# AQCA-Light-Control-uC-A0.net
KiCad netlist of a schematic drawn in Altium Designer
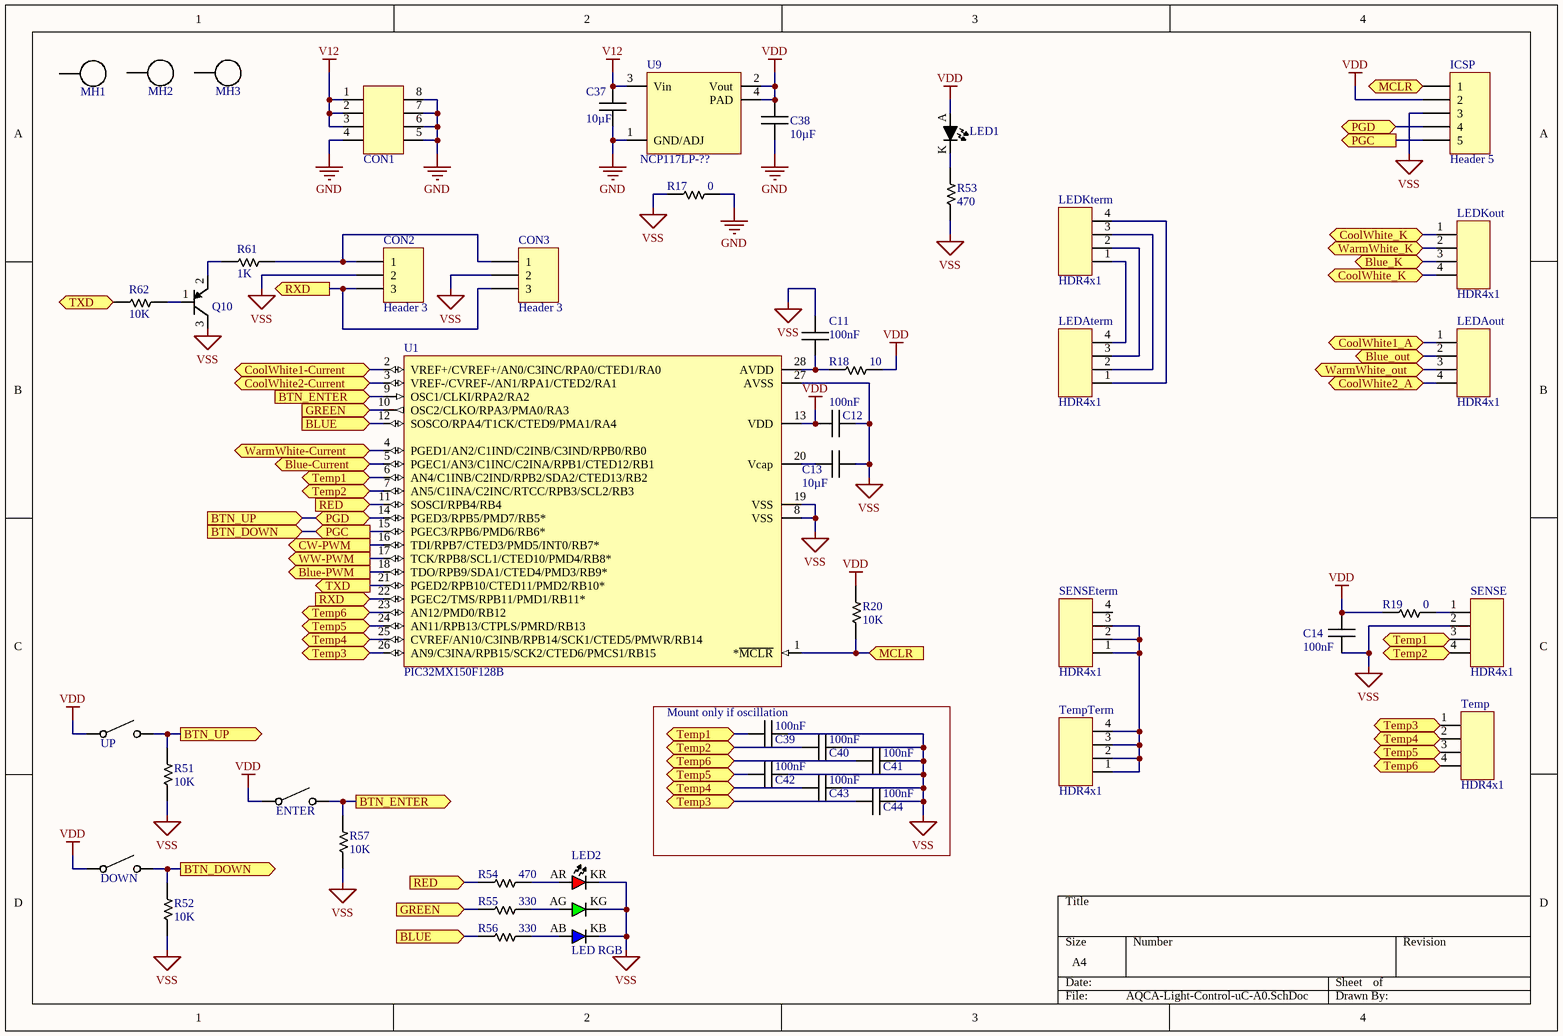
[diagram p0: AQCA-Light-Control-uC-A0.SchDoc]

(export (version "E")
  (design (tool "Eeschema 10.0.6"))
  (components
    (comp (ref "C11")
      (value "100nF")
      (footprint "CAPC1608N")
      (fields (field (name "VOLTAGE") "16V"))
      (libsource (lib "Megaxone") (part "Capacitor"))
    )
    (comp (ref "C12")
      (value "100nF")
      (footprint "CAPC1608N")
      (fields (field (name "VOLTAGE") "16V"))
      (libsource (lib "Megaxone") (part "Capacitor"))
    )
    (comp (ref "C13")
      (value "10µF")
      (footprint "CAPC2012N")
      (fields (field (name "VOLTAGE") "16V"))
      (libsource (lib "Megaxone") (part "Capacitor"))
    )
    (comp (ref "C14")
      (value "100nF")
      (footprint "CAPC1608N")
      (fields (field (name "VOLTAGE") "16V"))
      (libsource (lib "Megaxone") (part "Capacitor"))
    )
    (comp (ref "C37")
      (value "10µF")
      (footprint "CAPC3225N")
      (fields (field (name "VOLTAGE") "25V"))
      (libsource (lib "Megaxone") (part "Capacitor"))
    )
    (comp (ref "C38")
      (value "10µF")
      (footprint "CAPC3225N")
      (fields (field (name "VOLTAGE") "25V"))
      (libsource (lib "Megaxone") (part "Capacitor"))
    )
    (comp (ref "C39")
      (value "100nF")
      (footprint "CAPC1608N")
      (fields (field (name "VOLTAGE") "16V"))
      (libsource (lib "Megaxone") (part "Capacitor"))
    )
    (comp (ref "C40")
      (value "100nF")
      (footprint "CAPC1608N")
      (fields (field (name "VOLTAGE") "16V"))
      (libsource (lib "Megaxone") (part "Capacitor"))
    )
    (comp (ref "C41")
      (value "100nF")
      (footprint "CAPC1608N")
      (fields (field (name "VOLTAGE") "16V"))
      (libsource (lib "Megaxone") (part "Capacitor"))
    )
    (comp (ref "C42")
      (value "100nF")
      (footprint "CAPC1608N")
      (fields (field (name "VOLTAGE") "16V"))
      (libsource (lib "Megaxone") (part "Capacitor"))
    )
    (comp (ref "C43")
      (value "100nF")
      (footprint "CAPC1608N")
      (fields (field (name "VOLTAGE") "16V"))
      (libsource (lib "Megaxone") (part "Capacitor"))
    )
    (comp (ref "C44")
      (value "100nF")
      (footprint "CAPC1608N")
      (fields (field (name "VOLTAGE") "16V"))
      (libsource (lib "Megaxone") (part "Capacitor"))
    )
    (comp (ref "CON1")
      (value "Molex Mini-Fit 8pin")
      (footprint "Molex Mini-Fit 8pin")
      (libsource (lib "Megaxone") (part "Molex Mini-Fit 8pin"))
    )
    (comp (ref "CON2")
      (value "Header 3")
      (footprint "HDR1X3")
      (description "Header, 3-Pin")
      (fields (field (name "PUBLISHER") "Altium Limited"))
      (libsource (lib "Miscellaneous Connectors") (part "Header 3"))
    )
    (comp (ref "CON3")
      (value "Header 3")
      (footprint "HDR1X3")
      (description "Header, 3-Pin")
      (fields (field (name "PUBLISHER") "Altium Limited"))
      (libsource (lib "Miscellaneous Connectors") (part "Header 3"))
    )
    (comp (ref "DOWN")
      (value "Tact Button NO")
      (footprint "TACT SMD 4.5×4.5mm")
      (libsource (lib "Megaxone") (part "Tact Button NO"))
    )
    (comp (ref "ENTER")
      (value "Tact Button NO")
      (footprint "TACT SMD 4.5×4.5mm")
      (libsource (lib "Megaxone") (part "Tact Button NO"))
    )
    (comp (ref "ICSP")
      (value "Header 5")
      (footprint "HDR1X5")
      (description "Header, 5-Pin")
      (fields (field (name "PUBLISHER") "Altium Limited"))
      (libsource (lib "Miscellaneous Connectors") (part "Header 5"))
    )
    (comp (ref "LED1") (value "~") (footprint "LED 3216m") (libsource (lib "Megaxone") (part "LED")))
    (comp (ref "LED2")
      (value "LED RGB")
      (footprint "LED PLCC-6")
      (libsource (lib "Megaxone") (part "LED RGB"))
    )
    (comp (ref "LEDAout")
      (value "HDR4x1")
      (footprint "HDR4x1 EDGE female")
      (libsource (lib "") (part "HDR4x1_1"))
    )
    (comp (ref "LEDAterm")
      (value "HDR4x1")
      (footprint "HDR4x1 EDGE male")
      (libsource (lib "Megaxone") (part "HDR4x1"))
    )
    (comp (ref "LEDKout")
      (value "HDR4x1")
      (footprint "HDR4x1 EDGE female")
      (libsource (lib "") (part "HDR4x1_1"))
    )
    (comp (ref "LEDKterm")
      (value "HDR4x1")
      (footprint "HDR4x1 EDGE male")
      (libsource (lib "Megaxone") (part "HDR4x1"))
    )
    (comp (ref "MH1")
      (value "Mounting Hole")
      (footprint "Mount Hole 4-6.5")
      (libsource (lib "Megaxone") (part "Mounting Hole"))
    )
    (comp (ref "MH2")
      (value "Mounting Hole")
      (footprint "Mount Hole 4-6.5")
      (libsource (lib "Megaxone") (part "Mounting Hole"))
    )
    (comp (ref "MH3")
      (value "Mounting Hole")
      (footprint "Mount Hole 4-6.5")
      (libsource (lib "Megaxone") (part "Mounting Hole"))
    )
    (comp (ref "Q10") (value "*") (footprint "SOT23_N") (libsource (lib "Megaxone") (part "PNP")))
    (comp (ref "R17") (value "0") (footprint "RESC1608N") (libsource (lib "Megaxone") (part "Resistor")))
    (comp (ref "R18") (value "10") (footprint "RESC1608N") (libsource (lib "Megaxone") (part "Resistor")))
    (comp (ref "R19") (value "0") (footprint "RESC1608N") (libsource (lib "Megaxone") (part "Resistor")))
    (comp (ref "R20") (value "10K") (footprint "RESC1608N") (libsource (lib "") (part "Resistor_1")))
    (comp (ref "R51") (value "10K") (footprint "RESC1608N") (libsource (lib "") (part "Resistor_1")))
    (comp (ref "R52") (value "10K") (footprint "RESC1608N") (libsource (lib "") (part "Resistor_1")))
    (comp (ref "R53") (value "470") (footprint "RESC1608N") (libsource (lib "") (part "Resistor_1")))
    (comp (ref "R54") (value "470") (footprint "RESC1608N") (libsource (lib "Megaxone") (part "Resistor")))
    (comp (ref "R55") (value "330") (footprint "RESC1608N") (libsource (lib "Megaxone") (part "Resistor")))
    (comp (ref "R56") (value "330") (footprint "RESC1608N") (libsource (lib "Megaxone") (part "Resistor")))
    (comp (ref "R57") (value "10K") (footprint "RESC1608N") (libsource (lib "") (part "Resistor_1")))
    (comp (ref "R61") (value "1K") (footprint "RESC1608N") (libsource (lib "Megaxone") (part "Resistor")))
    (comp (ref "R62") (value "10K") (footprint "RESC1608N") (libsource (lib "Megaxone") (part "Resistor")))
    (comp (ref "SENSE")
      (value "HDR4x1")
      (footprint "HDR4x1 EDGE female")
      (libsource (lib "") (part "HDR4x1_1"))
    )
    (comp (ref "SENSEterm")
      (value "HDR4x1")
      (footprint "HDR4x1 EDGE male")
      (libsource (lib "Megaxone") (part "HDR4x1"))
    )
    (comp (ref "Temp")
      (value "HDR4x1")
      (footprint "HDR4x1 EDGE female")
      (libsource (lib "") (part "HDR4x1_1"))
    )
    (comp (ref "TempTerm")
      (value "HDR4x1")
      (footprint "HDR4x1 EDGE male")
      (libsource (lib "Megaxone") (part "HDR4x1"))
    )
    (comp (ref "U1")
      (value "PIC32MX150F128B")
      (footprint "SSOP28_N")
      (libsource (lib "Megaxone") (part "PIC32MX120FxxxB"))
    )
    (comp (ref "U9")
      (value "NCP117LP-??")
      (footprint "SOT223-4N")
      (libsource (lib "Megaxone") (part "NCP1117LP"))
    )
    (comp (ref "UP")
      (value "Tact Button NO")
      (footprint "TACT SMD 4.5×4.5mm")
      (libsource (lib "Megaxone") (part "Tact Button NO"))
    )
  )
  (nets
    (net (code "1") (name "/BLUE") (class "Default")
      (node (ref "R56") (pin "1") (pinfunction "1_1") (pintype "passive"))
      (node (ref "U1") (pin "12") (pinfunction "SOSCO/RPA4/T1CK/CTED9/PMA1/RA4_12") (pintype "bidirectional"))
    )
    (net (code "2") (name "/BTN_DOWN") (class "Default")
      (node (ref "DOWN") (pin "2") (pinfunction "2_2") (pintype "passive"))
      (node (ref "ICSP") (pin "5") (pinfunction "5_5") (pintype "passive"))
      (node (ref "R52") (pin "2") (pinfunction "2_2") (pintype "passive"))
      (node (ref "U1") (pin "15") (pinfunction "PGEC3/RPB6/PMD6/RB6*_15") (pintype "bidirectional"))
    )
    (net (code "3") (name "/BTN_ENTER") (class "Default")
      (node (ref "ENTER") (pin "2") (pinfunction "2_2") (pintype "passive"))
      (node (ref "R57") (pin "2") (pinfunction "2_2") (pintype "passive"))
      (node (ref "U1") (pin "9") (pinfunction "OSC1/CLKI/RPA2/RA2_9") (pintype "input"))
    )
    (net (code "4") (name "/BTN_UP") (class "Default")
      (node (ref "ICSP") (pin "4") (pinfunction "4_4") (pintype "passive"))
      (node (ref "R51") (pin "2") (pinfunction "2_2") (pintype "passive"))
      (node (ref "U1") (pin "14") (pinfunction "PGED3/RPB5/PMD7/RB5*_14") (pintype "bidirectional"))
      (node (ref "UP") (pin "2") (pinfunction "2_2") (pintype "passive"))
    )
    (net (code "5") (name "/Blue-Current") (class "Default")
      (node (ref "U1") (pin "5") (pinfunction "PGEC1/AN3/C1INC/C2INA/RPB1/CTED12/RB1_5") (pintype "bidirectional"))
    )
    (net (code "6") (name "/Blue-PWM") (class "Default")
      (node (ref "U1") (pin "18") (pinfunction "TDO/RPB9/SDA1/CTED4/PMD3/RB9*_18") (pintype "bidirectional"))
    )
    (net (code "7") (name "/Blue_K") (class "Default")
      (node (ref "LEDKout") (pin "3") (pinfunction "3_3") (pintype "passive"))
    )
    (net (code "8") (name "/Blue_out") (class "Default")
      (node (ref "LEDAout") (pin "2") (pinfunction "2_2") (pintype "passive"))
    )
    (net (code "9") (name "/CW-PWM") (class "Default")
      (node (ref "U1") (pin "16") (pinfunction "TDI/RPB7/CTED3/PMD5/INT0/RB7*_16") (pintype "bidirectional"))
    )
    (net (code "10") (name "/CoolWhite1-Current") (class "Default")
      (node (ref "U1") (pin "2") (pinfunction "VREF+/CVREF+/AN0/C3INC/RPA0/CTED1/RA0_2") (pintype "bidirectional"))
    )
    (net (code "11") (name "/CoolWhite1_A") (class "Default")
      (node (ref "LEDAout") (pin "1") (pinfunction "1_1") (pintype "passive"))
    )
    (net (code "12") (name "/CoolWhite2-Current") (class "Default")
      (node (ref "U1") (pin "3") (pinfunction "VREF-/CVREF-/AN1/RPA1/CTED2/RA1_3") (pintype "bidirectional"))
    )
    (net (code "13") (name "/CoolWhite2_A") (class "Default")
      (node (ref "LEDAout") (pin "4") (pinfunction "4_4") (pintype "passive"))
    )
    (net (code "14") (name "/CoolWhite_K") (class "Default")
      (node (ref "LEDKout") (pin "1") (pinfunction "1_1") (pintype "passive"))
      (node (ref "LEDKout") (pin "4") (pinfunction "4_4") (pintype "passive"))
    )
    (net (code "15") (name "/GREEN") (class "Default")
      (node (ref "R55") (pin "1") (pinfunction "1_1") (pintype "passive"))
      (node (ref "U1") (pin "10") (pinfunction "OSC2/CLKO/RPA3/PMA0/RA3_10") (pintype "output"))
    )
    (net (code "16") (name "/MCLR") (class "Default")
      (node (ref "ICSP") (pin "1") (pinfunction "1_1") (pintype "passive"))
      (node (ref "R20") (pin "1") (pinfunction "1_1") (pintype "passive"))
      (node (ref "U1") (pin "1") (pinfunction "*~{MCLR}_1") (pintype "input"))
    )
    (net (code "17") (name "/RED") (class "Default")
      (node (ref "R54") (pin "1") (pinfunction "1_1") (pintype "passive"))
      (node (ref "U1") (pin "11") (pinfunction "SOSCI/RPB4/RB4_11") (pintype "bidirectional"))
    )
    (net (code "18") (name "/RXD") (class "Default")
      (node (ref "CON2") (pin "3") (pinfunction "3_3") (pintype "passive"))
      (node (ref "CON3") (pin "3") (pinfunction "3_3") (pintype "passive"))
      (node (ref "U1") (pin "22") (pinfunction "PGEC2/TMS/RPB11/PMD1/RB11*_22") (pintype "bidirectional"))
    )
    (net (code "19") (name "/TXD") (class "Default")
      (node (ref "R62") (pin "1") (pinfunction "1_1") (pintype "passive"))
      (node (ref "U1") (pin "21") (pinfunction "PGED2/RPB10/CTED11/PMD2/RB10*_21") (pintype "bidirectional"))
    )
    (net (code "20") (name "/Temp1") (class "Default")
      (node (ref "C39") (pin "1") (pinfunction "1_1") (pintype "passive"))
      (node (ref "SENSE") (pin "3") (pinfunction "3_3") (pintype "passive"))
      (node (ref "U1") (pin "6") (pinfunction "AN4/C1INB/C2IND/RPB2/SDA2/CTED13/RB2_6") (pintype "bidirectional"))
    )
    (net (code "21") (name "/Temp2") (class "Default")
      (node (ref "C40") (pin "1") (pinfunction "1_1") (pintype "passive"))
      (node (ref "SENSE") (pin "4") (pinfunction "4_4") (pintype "passive"))
      (node (ref "U1") (pin "7") (pinfunction "AN5/C1INA/C2INC/RTCC/RPB3/SCL2/RB3_7") (pintype "bidirectional"))
    )
    (net (code "22") (name "/Temp3") (class "Default")
      (node (ref "C44") (pin "1") (pinfunction "1_1") (pintype "passive"))
      (node (ref "Temp") (pin "1") (pinfunction "1_1") (pintype "passive"))
      (node (ref "U1") (pin "26") (pinfunction "AN9/C3INA/RPB15/SCK2/CTED6/PMCS1/RB15_26") (pintype "bidirectional"))
    )
    (net (code "23") (name "/Temp4") (class "Default")
      (node (ref "C43") (pin "1") (pinfunction "1_1") (pintype "passive"))
      (node (ref "Temp") (pin "2") (pinfunction "2_2") (pintype "passive"))
      (node (ref "U1") (pin "25") (pinfunction "CVREF/AN10/C3INB/RPB14/SCK1/CTED5/PMWR/RB14_25") (pintype "bidirectional"))
    )
    (net (code "24") (name "/Temp5") (class "Default")
      (node (ref "C42") (pin "1") (pinfunction "1_1") (pintype "passive"))
      (node (ref "Temp") (pin "3") (pinfunction "3_3") (pintype "passive"))
      (node (ref "U1") (pin "24") (pinfunction "AN11/RPB13/CTPLS/PMRD/RB13_24") (pintype "bidirectional"))
    )
    (net (code "25") (name "/Temp6") (class "Default")
      (node (ref "C41") (pin "1") (pinfunction "1_1") (pintype "passive"))
      (node (ref "Temp") (pin "4") (pinfunction "4_4") (pintype "passive"))
      (node (ref "U1") (pin "23") (pinfunction "AN12/PMD0/RB12_23") (pintype "bidirectional"))
    )
    (net (code "26") (name "/WW-PWM") (class "Default")
      (node (ref "U1") (pin "17") (pinfunction "TCK/RPB8/SCL1/CTED10/PMD4/RB8*_17") (pintype "bidirectional"))
    )
    (net (code "27") (name "/WarmWhite-Current") (class "Default")
      (node (ref "U1") (pin "4") (pinfunction "PGED1/AN2/C1IND/C2INB/C3IND/RPB0/RB0_4") (pintype "bidirectional"))
    )
    (net (code "28") (name "/WarmWhite_K") (class "Default")
      (node (ref "LEDKout") (pin "2") (pinfunction "2_2") (pintype "passive"))
    )
    (net (code "29") (name "/WarmWhite_out") (class "Default")
      (node (ref "LEDAout") (pin "3") (pinfunction "3_3") (pintype "passive"))
    )
    (net (code "30") (name "GND") (class "Default")
      (node (ref "C37") (pin "1") (pinfunction "1_1") (pintype "passive"))
      (node (ref "C38") (pin "1") (pinfunction "1_1") (pintype "passive"))
      (node (ref "CON1") (pin "4") (pintype "power_in"))
      (node (ref "CON1") (pin "5") (pintype "power_in"))
      (node (ref "CON1") (pin "6") (pintype "power_in"))
      (node (ref "CON1") (pin "7") (pintype "power_in"))
      (node (ref "CON1") (pin "8") (pintype "power_in"))
      (node (ref "R17") (pin "2") (pinfunction "2_2") (pintype "passive"))
      (node (ref "U9") (pin "1") (pinfunction "GND/ADJ_1") (pintype "power_in"))
    )
    (net (code "31") (name "Net-(CON2-Pad1)") (class "Default")
      (node (ref "CON2") (pin "1") (pinfunction "1_1") (pintype "passive"))
      (node (ref "CON3") (pin "1") (pinfunction "1_1") (pintype "passive"))
      (node (ref "R61") (pin "2") (pinfunction "2_2") (pintype "passive"))
    )
    (net (code "32") (name "Net-(LED1-PadK)") (class "Default")
      (node (ref "LED1") (pin "K") (pinfunction "K_K") (pintype "passive"))
      (node (ref "R53") (pin "2") (pinfunction "2_2") (pintype "passive"))
    )
    (net (code "33") (name "Net-(LED2-PadAB)") (class "Default")
      (node (ref "LED2") (pin "AB") (pinfunction "AB_AB") (pintype "passive"))
      (node (ref "R56") (pin "2") (pinfunction "2_2") (pintype "passive"))
    )
    (net (code "34") (name "Net-(LED2-PadAG)") (class "Default")
      (node (ref "LED2") (pin "AG") (pinfunction "AG_AG") (pintype "passive"))
      (node (ref "R55") (pin "2") (pinfunction "2_2") (pintype "passive"))
    )
    (net (code "35") (name "Net-(LED2-PadAR)") (class "Default")
      (node (ref "LED2") (pin "AR") (pinfunction "AR_AR") (pintype "passive"))
      (node (ref "R54") (pin "2") (pinfunction "2_2") (pintype "passive"))
    )
    (net (code "36") (name "Net-(LEDAterm-Pad1)") (class "Default")
      (node (ref "LEDAterm") (pin "1") (pinfunction "1_1") (pintype "passive"))
      (node (ref "LEDKterm") (pin "4") (pinfunction "4_4") (pintype "passive"))
    )
    (net (code "37") (name "Net-(LEDAterm-Pad2)") (class "Default")
      (node (ref "LEDAterm") (pin "2") (pinfunction "2_2") (pintype "passive"))
      (node (ref "LEDKterm") (pin "3") (pinfunction "3_3") (pintype "passive"))
    )
    (net (code "38") (name "Net-(LEDAterm-Pad3)") (class "Default")
      (node (ref "LEDAterm") (pin "3") (pinfunction "3_3") (pintype "passive"))
      (node (ref "LEDKterm") (pin "2") (pinfunction "2_2") (pintype "passive"))
    )
    (net (code "39") (name "Net-(LEDAterm-Pad4)") (class "Default")
      (node (ref "LEDAterm") (pin "4") (pinfunction "4_4") (pintype "passive"))
      (node (ref "LEDKterm") (pin "1") (pinfunction "1_1") (pintype "passive"))
    )
    (net (code "40") (name "Net-(Q10-B)") (class "Default")
      (node (ref "Q10") (pin "1") (pinfunction "B_1") (pintype "passive"))
      (node (ref "R62") (pin "2") (pinfunction "2_2") (pintype "passive"))
    )
    (net (code "41") (name "Net-(Q10-E)") (class "Default")
      (node (ref "Q10") (pin "2") (pinfunction "E_2") (pintype "passive"))
      (node (ref "R61") (pin "1") (pinfunction "1_1") (pintype "passive"))
    )
    (net (code "42") (name "Net-(R19-Pad2)") (class "Default")
      (node (ref "R19") (pin "2") (pinfunction "2_2") (pintype "passive"))
      (node (ref "SENSE") (pin "1") (pinfunction "1_1") (pintype "passive"))
    )
    (net (code "43") (name "Net-(SENSEterm-Pad1)") (class "Default")
      (node (ref "SENSEterm") (pin "1") (pinfunction "1_1") (pintype "passive"))
      (node (ref "SENSEterm") (pin "2") (pinfunction "2_2") (pintype "passive"))
      (node (ref "SENSEterm") (pin "3") (pinfunction "3_3") (pintype "passive"))
      (node (ref "TempTerm") (pin "1") (pinfunction "1_1") (pintype "passive"))
      (node (ref "TempTerm") (pin "2") (pinfunction "2_2") (pintype "passive"))
      (node (ref "TempTerm") (pin "3") (pinfunction "3_3") (pintype "passive"))
      (node (ref "TempTerm") (pin "4") (pinfunction "4_4") (pintype "passive"))
    )
    (net (code "44") (name "Net-(U1-AVDD)") (class "Default")
      (node (ref "C11") (pin "1") (pinfunction "1_1") (pintype "passive"))
      (node (ref "R18") (pin "1") (pinfunction "1_1") (pintype "passive"))
      (node (ref "U1") (pin "28") (pinfunction "AVDD_28") (pintype "power_in"))
    )
    (net (code "45") (name "Net-(U1-Vcap)") (class "Default")
      (node (ref "C13") (pin "1") (pinfunction "1_1") (pintype "passive"))
      (node (ref "U1") (pin "20") (pinfunction "Vcap_20") (pintype "power_in"))
    )
    (net (code "46") (name "V12") (class "Default")
      (node (ref "C37") (pin "2") (pinfunction "2_2") (pintype "passive"))
      (node (ref "CON1") (pin "1") (pintype "power_in"))
      (node (ref "CON1") (pin "2") (pintype "power_in"))
      (node (ref "CON1") (pin "3") (pintype "power_in"))
      (node (ref "U9") (pin "3") (pinfunction "Vin_3") (pintype "power_in"))
    )
    (net (code "47") (name "VDD") (class "Default")
      (node (ref "C12") (pin "1") (pinfunction "1_1") (pintype "passive"))
      (node (ref "C14") (pin "2") (pinfunction "2_2") (pintype "passive"))
      (node (ref "C38") (pin "2") (pinfunction "2_2") (pintype "passive"))
      (node (ref "DOWN") (pin "1") (pinfunction "1_1") (pintype "passive"))
      (node (ref "ENTER") (pin "1") (pinfunction "1_1") (pintype "passive"))
      (node (ref "ICSP") (pin "2") (pinfunction "2_2") (pintype "passive"))
      (node (ref "LED1") (pin "A") (pinfunction "A_A") (pintype "passive"))
      (node (ref "R18") (pin "2") (pinfunction "2_2") (pintype "passive"))
      (node (ref "R19") (pin "1") (pinfunction "1_1") (pintype "passive"))
      (node (ref "R20") (pin "2") (pinfunction "2_2") (pintype "passive"))
      (node (ref "U1") (pin "13") (pinfunction "VDD_13") (pintype "power_in"))
      (node (ref "U9") (pin "2") (pinfunction "Vout_2") (pintype "power_in"))
      (node (ref "U9") (pin "4") (pinfunction "PAD_4") (pintype "power_in"))
      (node (ref "UP") (pin "1") (pinfunction "1_1") (pintype "passive"))
    )
    (net (code "48") (name "VSS") (class "Default")
      (node (ref "C11") (pin "2") (pinfunction "2_2") (pintype "passive"))
      (node (ref "C12") (pin "2") (pinfunction "2_2") (pintype "passive"))
      (node (ref "C13") (pin "2") (pinfunction "2_2") (pintype "passive"))
      (node (ref "C14") (pin "1") (pinfunction "1_1") (pintype "passive"))
      (node (ref "C39") (pin "2") (pinfunction "2_2") (pintype "passive"))
      (node (ref "C40") (pin "2") (pinfunction "2_2") (pintype "passive"))
      (node (ref "C41") (pin "2") (pinfunction "2_2") (pintype "passive"))
      (node (ref "C42") (pin "2") (pinfunction "2_2") (pintype "passive"))
      (node (ref "C43") (pin "2") (pinfunction "2_2") (pintype "passive"))
      (node (ref "C44") (pin "2") (pinfunction "2_2") (pintype "passive"))
      (node (ref "CON2") (pin "2") (pinfunction "2_2") (pintype "passive"))
      (node (ref "CON3") (pin "2") (pinfunction "2_2") (pintype "passive"))
      (node (ref "ICSP") (pin "3") (pinfunction "3_3") (pintype "passive"))
      (node (ref "LED2") (pin "KB") (pinfunction "KB_KB") (pintype "passive"))
      (node (ref "LED2") (pin "KG") (pinfunction "KG_KG") (pintype "passive"))
      (node (ref "LED2") (pin "KR") (pinfunction "KR_KR") (pintype "passive"))
      (node (ref "Q10") (pin "3") (pinfunction "C_3") (pintype "passive"))
      (node (ref "R17") (pin "1") (pinfunction "1_1") (pintype "passive"))
      (node (ref "R51") (pin "1") (pinfunction "1_1") (pintype "passive"))
      (node (ref "R52") (pin "1") (pinfunction "1_1") (pintype "passive"))
      (node (ref "R53") (pin "1") (pinfunction "1_1") (pintype "passive"))
      (node (ref "R57") (pin "1") (pinfunction "1_1") (pintype "passive"))
      (node (ref "SENSE") (pin "2") (pinfunction "2_2") (pintype "passive"))
      (node (ref "U1") (pin "19") (pinfunction "VSS_19") (pintype "power_in"))
      (node (ref "U1") (pin "27") (pinfunction "AVSS_27") (pintype "power_in"))
      (node (ref "U1") (pin "8") (pinfunction "VSS_8") (pintype "power_in"))
    )
    (net (code "49") (name "unconnected-(MH1-Pad1)") (class "Default")
      (node (ref "MH1") (pin "1") (pintype "power_in"))
    )
    (net (code "50") (name "unconnected-(MH2-Pad1)") (class "Default")
      (node (ref "MH2") (pin "1") (pintype "power_in"))
    )
    (net (code "51") (name "unconnected-(MH3-Pad1)") (class "Default")
      (node (ref "MH3") (pin "1") (pintype "power_in"))
    )
    (net (code "52") (name "unconnected-(SENSEterm-Pad4)") (class "Default")
      (node (ref "SENSEterm") (pin "4") (pinfunction "4_4") (pintype "passive"))
    )
  )
)
